# 1-Schematic_VGA_Disconnector.net
KiCad netlist of a schematic drawn in EasyEDA
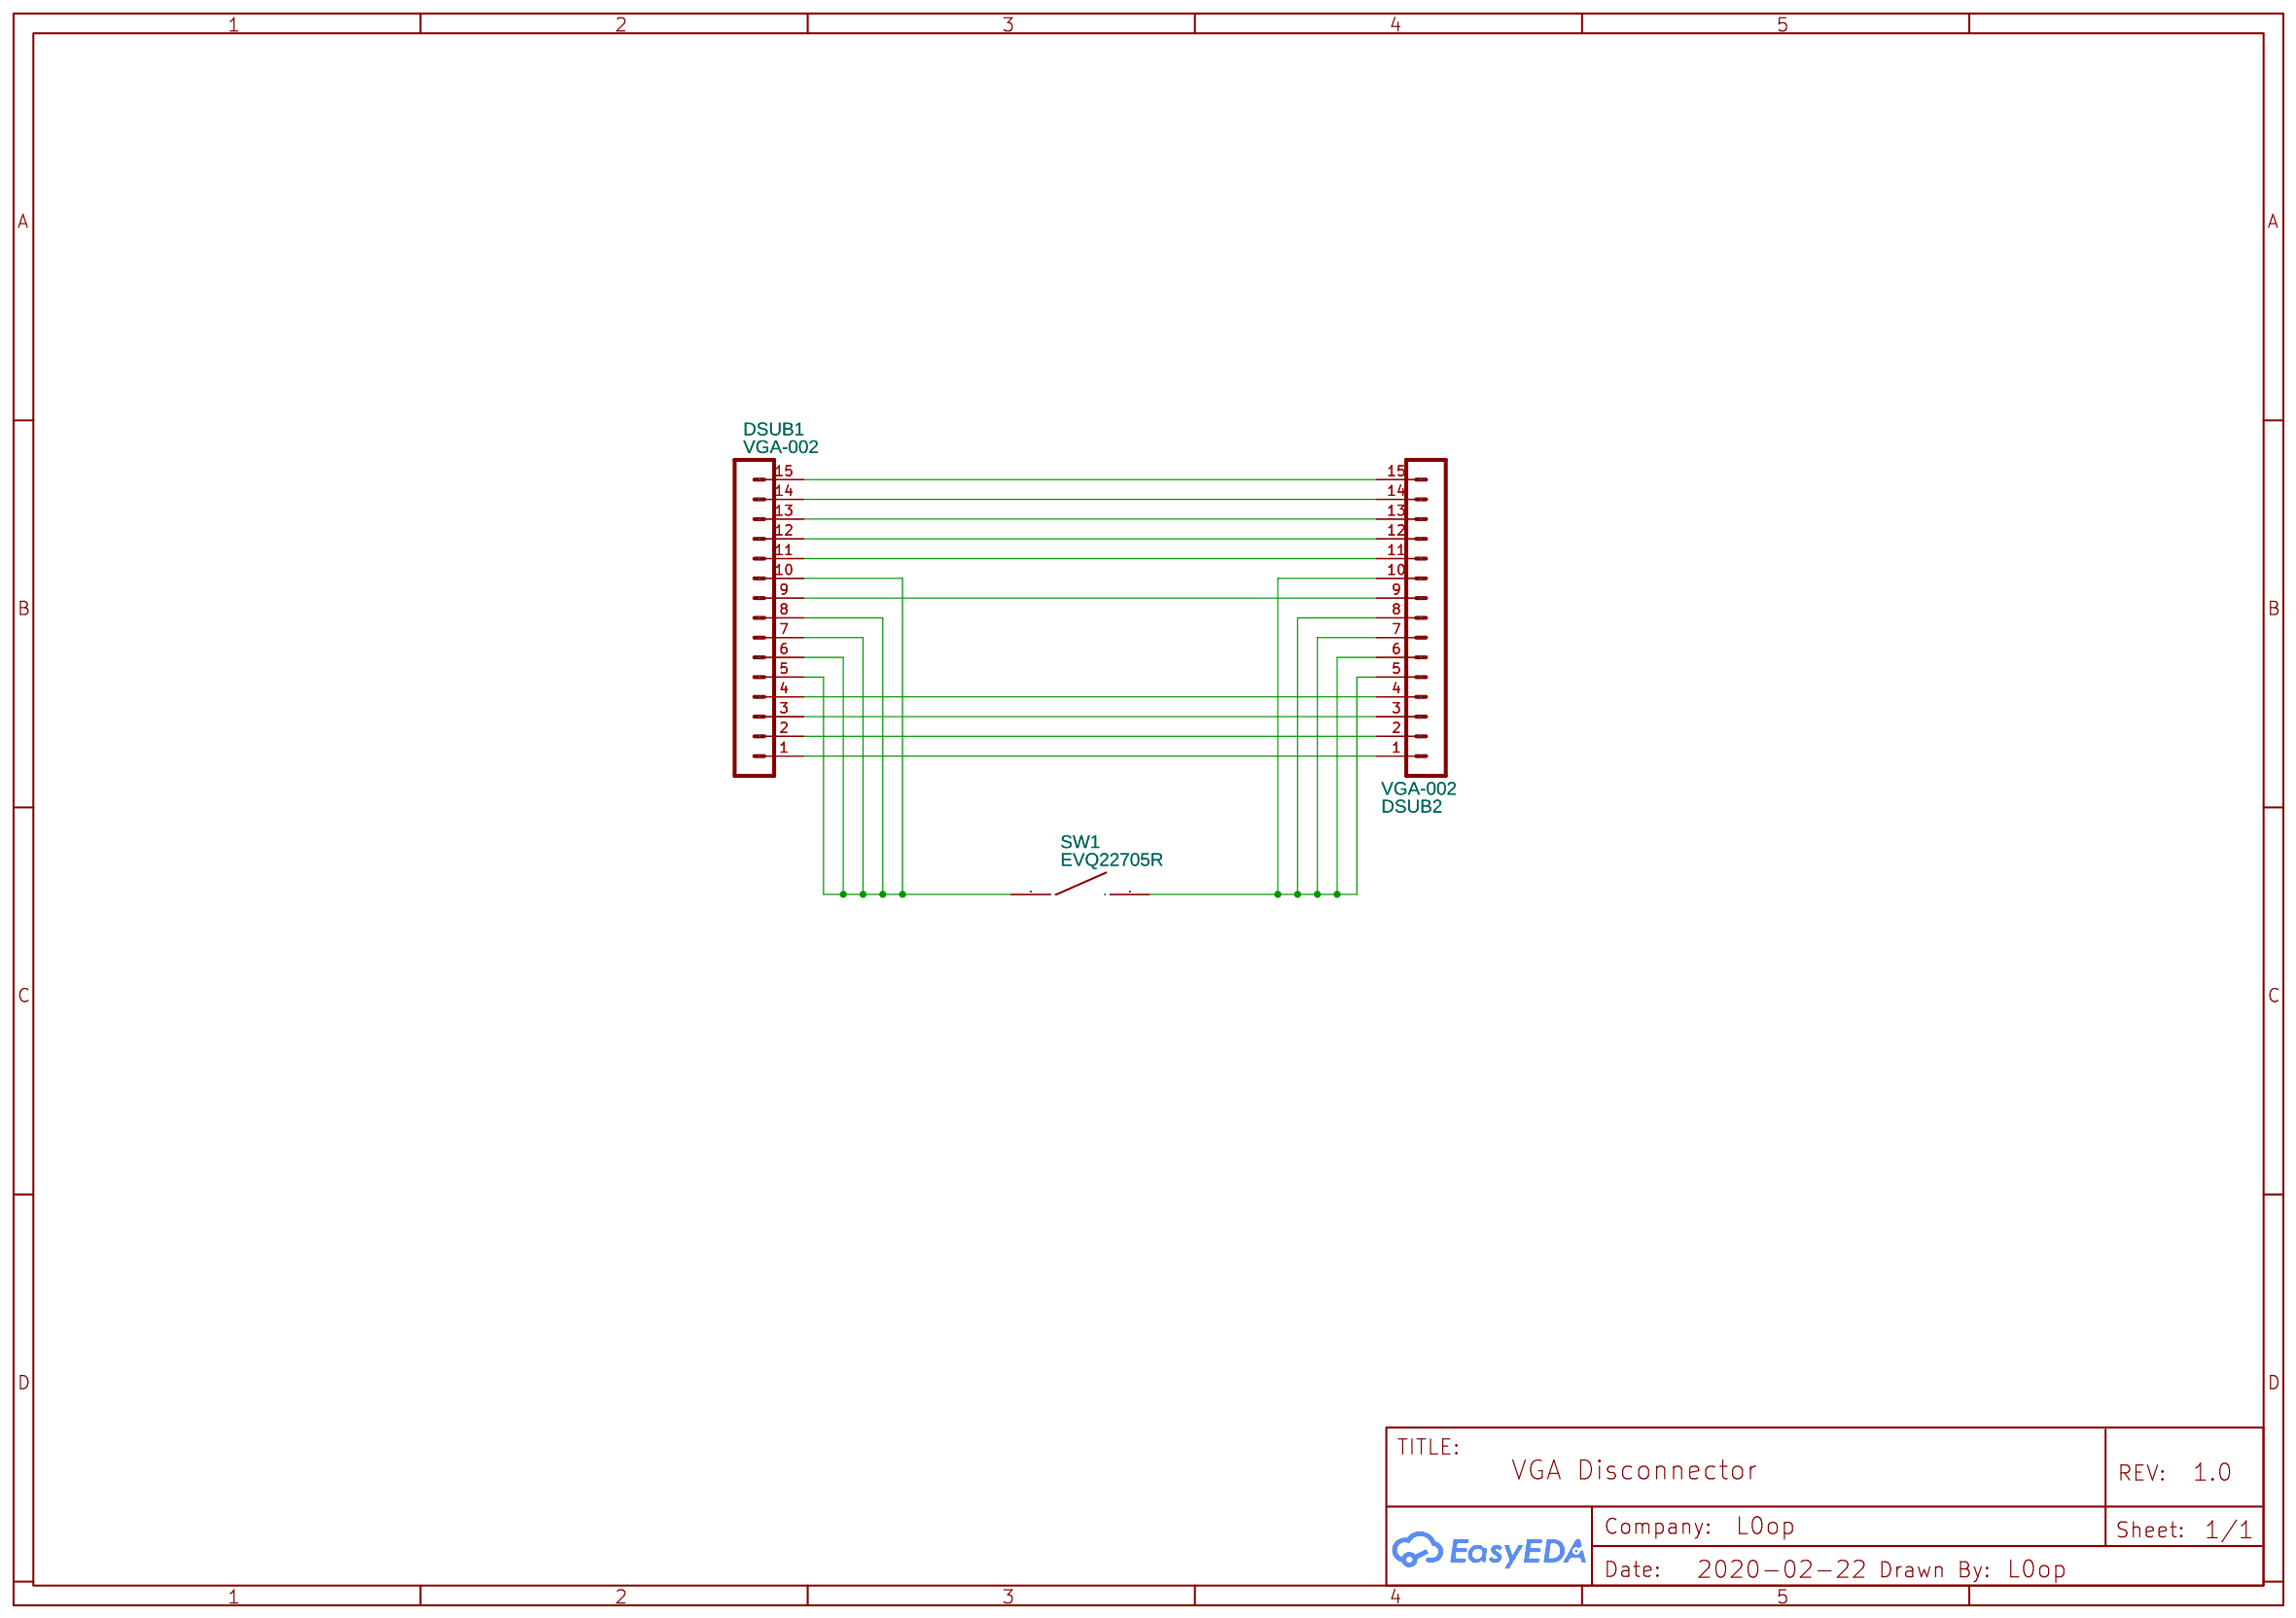
[diagram p0: schematic sheet]

(export (version "E")
  (design (tool "Eeschema 10.0.6"))
  (components
    (comp (ref "DSUB1")
      (value "VGA-002")
      (fields (field (name "BOM_Supplier Part") "C138387"))
      (libsource (lib "") (part "VGA-002"))
    )
    (comp (ref "DSUB2")
      (value "VGA-002")
      (fields (field (name "BOM_Supplier Part") "C138387"))
      (libsource (lib "") (part "VGA-002_1"))
    )
    (comp (ref "SW1")
      (value "EVQ22705R")
      (fields (field (name "BOM_Supplier Part") "C79156"))
      (libsource (lib "") (part "EVQ22705R"))
    )
  )
  (nets
    (net (code "1") (name "Net-(DSUB1-Pad1)") (class "Default")
      (node (ref "DSUB1") (pin "1") (pinfunction "1_1") (pintype "unspecified"))
      (node (ref "DSUB2") (pin "1") (pinfunction "1_1") (pintype "unspecified"))
    )
    (net (code "2") (name "Net-(DSUB1-Pad2)") (class "Default")
      (node (ref "DSUB1") (pin "2") (pinfunction "2_2") (pintype "unspecified"))
      (node (ref "DSUB2") (pin "2") (pinfunction "2_2") (pintype "unspecified"))
    )
    (net (code "3") (name "Net-(DSUB1-Pad3)") (class "Default")
      (node (ref "DSUB1") (pin "3") (pinfunction "3_3") (pintype "unspecified"))
      (node (ref "DSUB2") (pin "3") (pinfunction "3_3") (pintype "unspecified"))
    )
    (net (code "4") (name "Net-(DSUB1-Pad4)") (class "Default")
      (node (ref "DSUB1") (pin "4") (pinfunction "4_4") (pintype "unspecified"))
      (node (ref "DSUB2") (pin "4") (pinfunction "4_4") (pintype "unspecified"))
    )
    (net (code "5") (name "Net-(DSUB1-Pad9)") (class "Default")
      (node (ref "DSUB1") (pin "9") (pinfunction "9_9") (pintype "unspecified"))
      (node (ref "DSUB2") (pin "9") (pinfunction "9_9") (pintype "unspecified"))
    )
    (net (code "6") (name "Net-(DSUB1-Pad10)") (class "Default")
      (node (ref "DSUB1") (pin "10") (pinfunction "10_10") (pintype "unspecified"))
      (node (ref "DSUB1") (pin "5") (pinfunction "5_5") (pintype "unspecified"))
      (node (ref "DSUB1") (pin "6") (pinfunction "6_6") (pintype "unspecified"))
      (node (ref "DSUB1") (pin "7") (pinfunction "7_7") (pintype "unspecified"))
      (node (ref "DSUB1") (pin "8") (pinfunction "8_8") (pintype "unspecified"))
      (node (ref "SW1") (pin "1") (pinfunction "1_1") (pintype "input"))
    )
    (net (code "7") (name "Net-(DSUB1-Pad11)") (class "Default")
      (node (ref "DSUB1") (pin "11") (pinfunction "11_11") (pintype "unspecified"))
      (node (ref "DSUB2") (pin "11") (pinfunction "11_11") (pintype "unspecified"))
    )
    (net (code "8") (name "Net-(DSUB1-Pad12)") (class "Default")
      (node (ref "DSUB1") (pin "12") (pinfunction "12_12") (pintype "unspecified"))
      (node (ref "DSUB2") (pin "12") (pinfunction "12_12") (pintype "unspecified"))
    )
    (net (code "9") (name "Net-(DSUB1-Pad13)") (class "Default")
      (node (ref "DSUB1") (pin "13") (pinfunction "13_13") (pintype "unspecified"))
      (node (ref "DSUB2") (pin "13") (pinfunction "13_13") (pintype "unspecified"))
    )
    (net (code "10") (name "Net-(DSUB1-Pad14)") (class "Default")
      (node (ref "DSUB1") (pin "14") (pinfunction "14_14") (pintype "unspecified"))
      (node (ref "DSUB2") (pin "14") (pinfunction "14_14") (pintype "unspecified"))
    )
    (net (code "11") (name "Net-(DSUB1-Pad15)") (class "Default")
      (node (ref "DSUB1") (pin "15") (pinfunction "15_15") (pintype "unspecified"))
      (node (ref "DSUB2") (pin "15") (pinfunction "15_15") (pintype "unspecified"))
    )
    (net (code "12") (name "Net-(DSUB2-Pad10)") (class "Default")
      (node (ref "DSUB2") (pin "10") (pinfunction "10_10") (pintype "unspecified"))
      (node (ref "DSUB2") (pin "5") (pinfunction "5_5") (pintype "unspecified"))
      (node (ref "DSUB2") (pin "6") (pinfunction "6_6") (pintype "unspecified"))
      (node (ref "DSUB2") (pin "7") (pinfunction "7_7") (pintype "unspecified"))
      (node (ref "DSUB2") (pin "8") (pinfunction "8_8") (pintype "unspecified"))
      (node (ref "SW1") (pin "2") (pinfunction "2_2") (pintype "input"))
    )
  )
)
